# CAN.net
KiCad netlist of a schematic drawn in Altium Designer
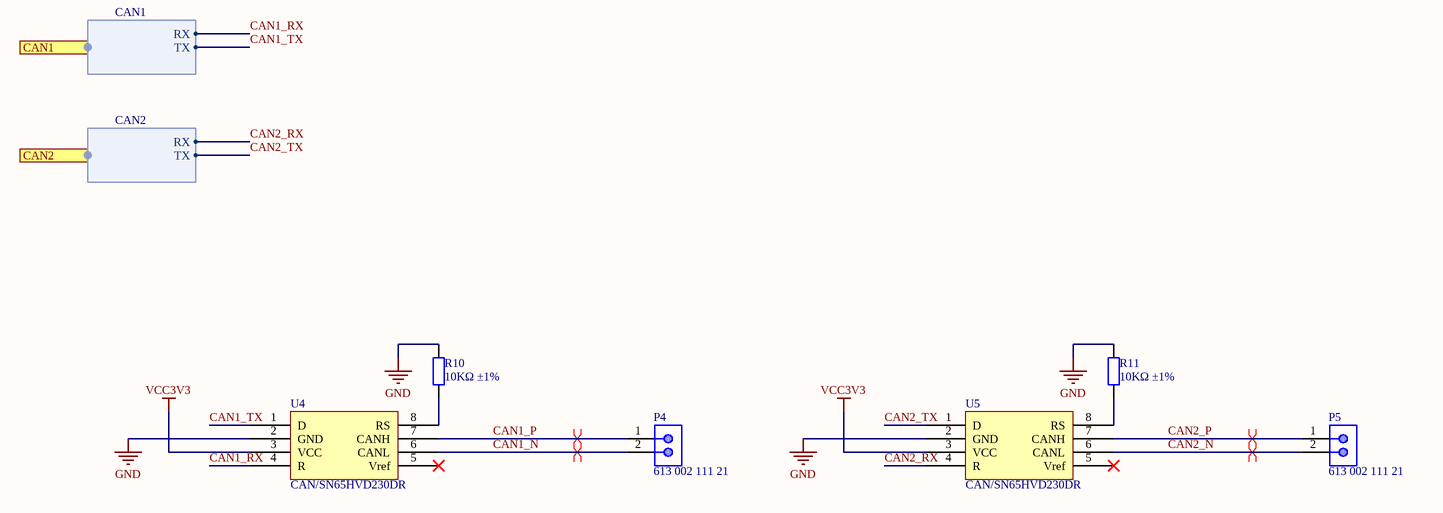
[diagram p0: CAN.SchDoc]

(export (version "E")
  (design (tool "Eeschema 10.0.6"))
  (components
    (comp (ref "P4")
      (value "613 002 111 21")
      (footprint "WE-61300211121_V")
      (libsource (lib "Altium Content Vault") (part "CN-1P-M-R2"))
    )
    (comp (ref "P5")
      (value "613 002 111 21")
      (footprint "WE-61300211121_V")
      (libsource (lib "Altium Content Vault") (part "CN-1P-M-R2"))
    )
    (comp (ref "R10")
      (value "10KΩ ±1%")
      (footprint "0402_R")
      (description "Chip resistor")
      (fields (field (name "MANUFACTURER") "Uniroyal Elec") (field (name "PARTNUMBER") "0402WGF1002TCE"))
      (libsource (lib "Miscellaneous Devices LC") (part "0402 10K (1002) 1%"))
    )
    (comp (ref "R11")
      (value "10KΩ ±1%")
      (footprint "0402_R")
      (description "Chip resistor")
      (fields (field (name "MANUFACTURER") "Uniroyal Elec") (field (name "PARTNUMBER") "0402WGF1002TCE"))
      (libsource (lib "Miscellaneous Devices LC") (part "0402 10K (1002) 1%"))
    )
    (comp (ref "U4")
      (value "CAN/SN65HVD230DR")
      (footprint "SOIC-8_150mil")
      (description "CAN")
      (libsource (lib "Miscellaneous Devices LC") (part "CAN/SN65HVD230DR_[C12084]"))
    )
    (comp (ref "U5")
      (value "CAN/SN65HVD230DR")
      (footprint "SOIC-8_150mil")
      (description "CAN")
      (libsource (lib "Miscellaneous Devices LC") (part "CAN/SN65HVD230DR_[C12084]"))
    )
  )
  (nets
    (net (code "3") (name "/CAN1_N") (class "Default")
      (node (ref "P4") (pin "2") (pinfunction "2_2") (pintype "passive"))
      (node (ref "U4") (pin "6") (pinfunction "CANL_6") (pintype "passive"))
    )
    (net (code "4") (name "/CAN1_P") (class "Default")
      (node (ref "P4") (pin "1") (pinfunction "1_1") (pintype "passive"))
      (node (ref "U4") (pin "7") (pinfunction "CANH_7") (pintype "passive"))
    )
    (net (code "5") (name "/CAN1_RX") (class "Default")
      (node (ref "U4") (pin "4") (pinfunction "R_4") (pintype "passive"))
    )
    (net (code "6") (name "/CAN1_TX") (class "Default")
      (node (ref "U4") (pin "1") (pinfunction "D_1") (pintype "passive"))
    )
    (net (code "7") (name "/CAN2_N") (class "Default")
      (node (ref "P5") (pin "2") (pinfunction "2_2") (pintype "passive"))
      (node (ref "U5") (pin "6") (pinfunction "CANL_6") (pintype "passive"))
    )
    (net (code "8") (name "/CAN2_P") (class "Default")
      (node (ref "P5") (pin "1") (pinfunction "1_1") (pintype "passive"))
      (node (ref "U5") (pin "7") (pinfunction "CANH_7") (pintype "passive"))
    )
    (net (code "9") (name "/CAN2_RX") (class "Default")
      (node (ref "U5") (pin "4") (pinfunction "R_4") (pintype "passive"))
    )
    (net (code "10") (name "/CAN2_TX") (class "Default")
      (node (ref "U5") (pin "1") (pinfunction "D_1") (pintype "passive"))
    )
    (net (code "13") (name "GND") (class "Default")
      (node (ref "R10") (pin "2") (pinfunction "2_2") (pintype "passive"))
      (node (ref "R11") (pin "2") (pinfunction "2_2") (pintype "passive"))
      (node (ref "U4") (pin "2") (pinfunction "GND_2") (pintype "passive"))
      (node (ref "U5") (pin "2") (pinfunction "GND_2") (pintype "passive"))
    )
    (net (code "14") (name "Net-(U4-RS)") (class "Default")
      (node (ref "R10") (pin "1") (pinfunction "1_1") (pintype "passive"))
      (node (ref "U4") (pin "8") (pinfunction "RS_8") (pintype "passive"))
    )
    (net (code "15") (name "Net-(U5-RS)") (class "Default")
      (node (ref "R11") (pin "1") (pinfunction "1_1") (pintype "passive"))
      (node (ref "U5") (pin "8") (pinfunction "RS_8") (pintype "passive"))
    )
    (net (code "16") (name "VCC3V3") (class "Default")
      (node (ref "U4") (pin "3") (pinfunction "VCC_3") (pintype "passive"))
      (node (ref "U5") (pin "3") (pinfunction "VCC_3") (pintype "passive"))
    )
    (net (code "17") (name "unconnected-(U4-Vref-Pad5)") (class "Default")
      (node (ref "U4") (pin "5") (pinfunction "Vref_5") (pintype "passive+no_connect"))
    )
    (net (code "18") (name "unconnected-(U5-Vref-Pad5)") (class "Default")
      (node (ref "U5") (pin "5") (pinfunction "Vref_5") (pintype "passive+no_connect"))
    )
  )
)
